# Mechanical.net
KiCad netlist of a schematic drawn in Altium Designer
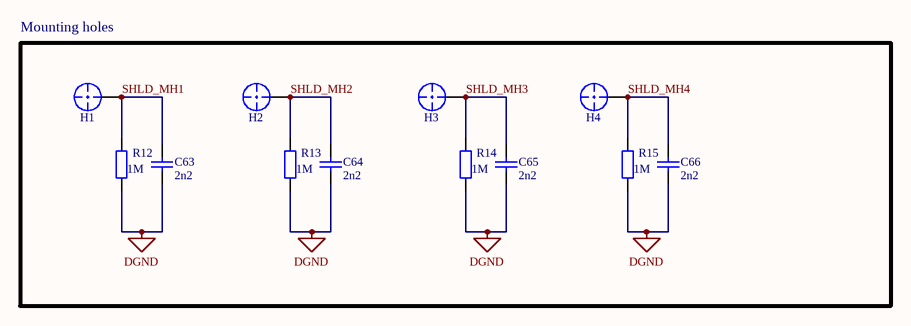
[diagram p0: Mechanical.SchDoc]

(export (version "E")
  (design (tool "Eeschema 10.0.6"))
  (components
    (comp (ref "C63")
      (value "2n2")
      (footprint "0603")
      (description "CAP CER 39PF 50V C0G/NP0 0603")
      (fields (field (name "MANUFACTURER PART NUMBER") "720-VJ0603A390GXACW1BCCT-ND"))
      (libsource (lib "Miscellaneous Devices") (part "Cap"))
    )
    (comp (ref "C64")
      (value "2n2")
      (footprint "0603")
      (description "CAP CER 39PF 50V C0G/NP0 0603")
      (fields (field (name "MANUFACTURER PART NUMBER") "720-VJ0603A390GXACW1BCCT-ND"))
      (libsource (lib "Miscellaneous Devices") (part "Cap"))
    )
    (comp (ref "C65")
      (value "2n2")
      (footprint "0603")
      (description "CAP CER 39PF 50V C0G/NP0 0603")
      (fields (field (name "MANUFACTURER PART NUMBER") "720-VJ0603A390GXACW1BCCT-ND"))
      (libsource (lib "Miscellaneous Devices") (part "Cap"))
    )
    (comp (ref "C66")
      (value "2n2")
      (footprint "0603")
      (description "CAP CER 39PF 50V C0G/NP0 0603")
      (fields (field (name "MANUFACTURER PART NUMBER") "720-VJ0603A390GXACW1BCCT-ND"))
      (libsource (lib "Miscellaneous Devices") (part "Cap"))
    )
    (comp (ref "H1")
      (value "Hole_Mount")
      (footprint "HoleMount")
      (libsource (lib "Transmitter") (part "Hole_Mount"))
    )
    (comp (ref "H2")
      (value "Hole_Mount")
      (footprint "HoleMount")
      (libsource (lib "Transmitter") (part "Hole_Mount"))
    )
    (comp (ref "H3")
      (value "Hole_Mount")
      (footprint "HoleMount")
      (libsource (lib "Transmitter") (part "Hole_Mount"))
    )
    (comp (ref "H4")
      (value "Hole_Mount")
      (footprint "HoleMount")
      (libsource (lib "Transmitter") (part "Hole_Mount"))
    )
    (comp (ref "R12")
      (value "1M")
      (footprint "0603")
      (description "RES 100 KOHMS 0.5% 1/10W 0603")
      (fields (field (name "MANUFACTURER PART NUMBER") "P123902CT-ND"))
      (libsource (lib "Miscellaneous Devices") (part "Res2"))
    )
    (comp (ref "R13")
      (value "1M")
      (footprint "0603")
      (description "RES 100 KOHMS 0.5% 1/10W 0603")
      (fields (field (name "MANUFACTURER PART NUMBER") "P123902CT-ND"))
      (libsource (lib "Miscellaneous Devices") (part "Res2"))
    )
    (comp (ref "R14")
      (value "1M")
      (footprint "0603")
      (description "RES 100 KOHMS 0.5% 1/10W 0603")
      (fields (field (name "MANUFACTURER PART NUMBER") "P123902CT-ND"))
      (libsource (lib "Miscellaneous Devices") (part "Res2"))
    )
    (comp (ref "R15")
      (value "1M")
      (footprint "0603")
      (description "RES 100 KOHMS 0.5% 1/10W 0603")
      (fields (field (name "MANUFACTURER PART NUMBER") "P123902CT-ND"))
      (libsource (lib "Miscellaneous Devices") (part "Res2"))
    )
  )
  (nets
    (net (code "1") (name "/SHLD_MH1") (class "Default")
      (node (ref "C63") (pin "2") (pinfunction "2_2") (pintype "passive"))
      (node (ref "H1") (pin "1") (pinfunction "CONNECT_TO_1") (pintype "power_in"))
      (node (ref "R12") (pin "2") (pinfunction "2_2") (pintype "passive"))
    )
    (net (code "2") (name "/SHLD_MH2") (class "Default")
      (node (ref "C64") (pin "2") (pinfunction "2_2") (pintype "passive"))
      (node (ref "H2") (pin "1") (pinfunction "CONNECT_TO_1") (pintype "power_in"))
      (node (ref "R13") (pin "2") (pinfunction "2_2") (pintype "passive"))
    )
    (net (code "3") (name "/SHLD_MH3") (class "Default")
      (node (ref "C65") (pin "2") (pinfunction "2_2") (pintype "passive"))
      (node (ref "H3") (pin "1") (pinfunction "CONNECT_TO_1") (pintype "power_in"))
      (node (ref "R14") (pin "2") (pinfunction "2_2") (pintype "passive"))
    )
    (net (code "4") (name "/SHLD_MH4") (class "Default")
      (node (ref "C66") (pin "2") (pinfunction "2_2") (pintype "passive"))
      (node (ref "H4") (pin "1") (pinfunction "CONNECT_TO_1") (pintype "power_in"))
      (node (ref "R15") (pin "2") (pinfunction "2_2") (pintype "passive"))
    )
    (net (code "5") (name "DGND") (class "Default")
      (node (ref "C63") (pin "1") (pinfunction "1_1") (pintype "passive"))
      (node (ref "C64") (pin "1") (pinfunction "1_1") (pintype "passive"))
      (node (ref "C65") (pin "1") (pinfunction "1_1") (pintype "passive"))
      (node (ref "C66") (pin "1") (pinfunction "1_1") (pintype "passive"))
      (node (ref "R12") (pin "1") (pinfunction "1_1") (pintype "passive"))
      (node (ref "R13") (pin "1") (pinfunction "1_1") (pintype "passive"))
      (node (ref "R14") (pin "1") (pinfunction "1_1") (pintype "passive"))
      (node (ref "R15") (pin "1") (pinfunction "1_1") (pintype "passive"))
    )
  )
)
